# BATT_INPUT_REVISION.net
KiCad netlist of a schematic drawn in EAGLE
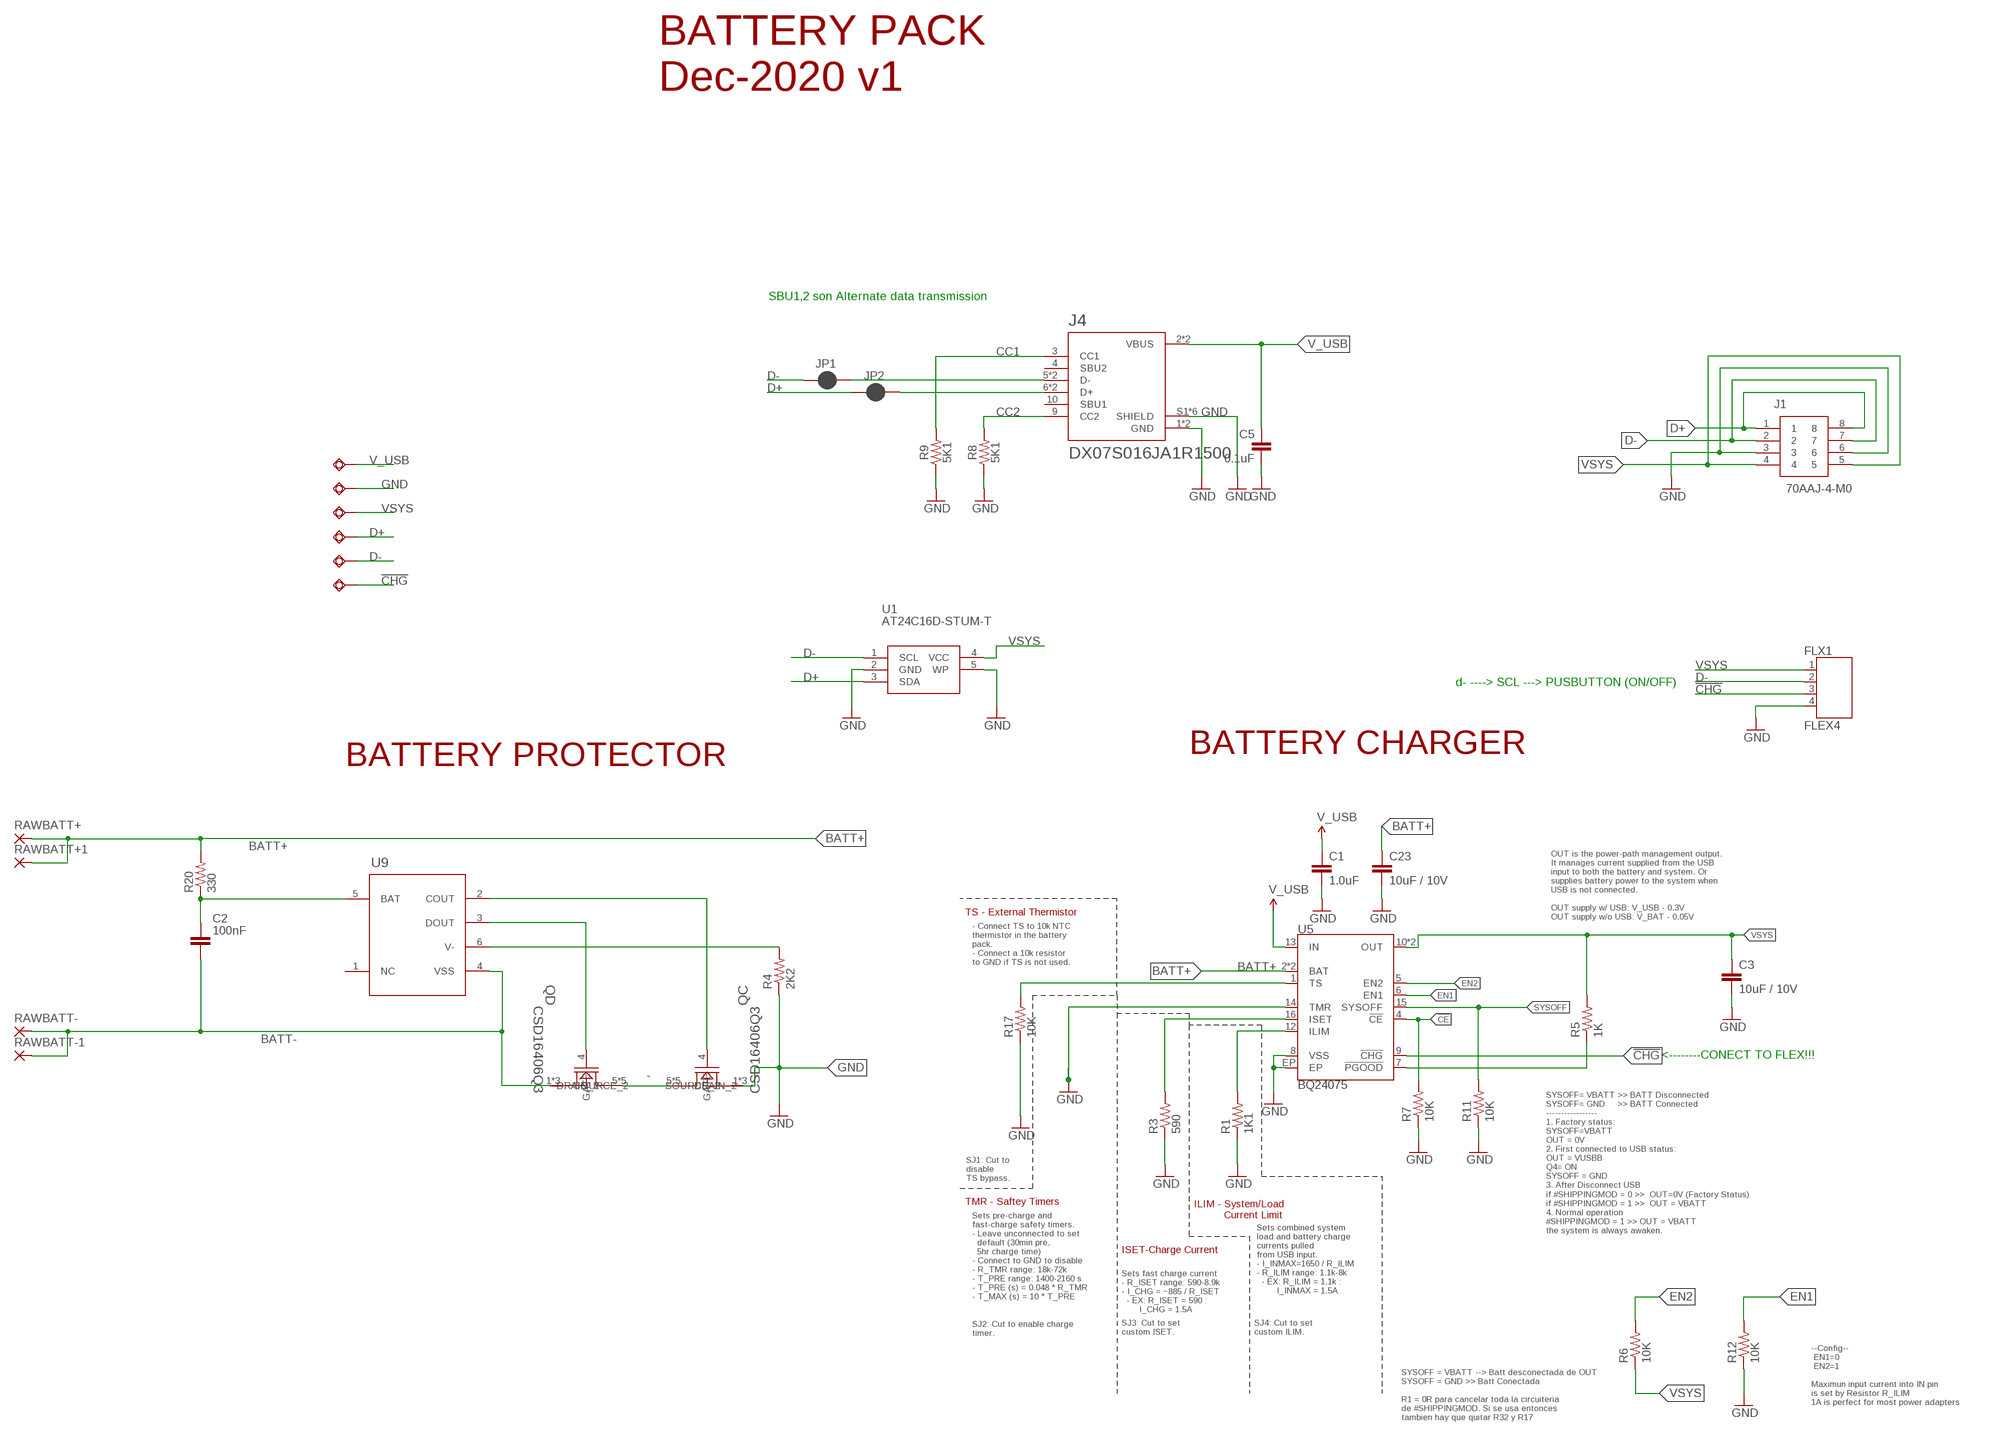
[diagram p0: schematic, sheet 1]

(export (version "E")
  (design (tool "Eeschema 10.0.6"))
  (components
    (comp (ref "!CHG!")
      (value "TESTPAD_TPSQB1,27")
      (footprint "eagle-import:TESTPAD_B1,27")
      (libsource (lib "eagle-import") (part "TESTPAD_TPSQB1,27"))
    )
    (comp (ref "C1")
      (value "1.0uF")
      (footprint "eagle-import:0603")
      (libsource (lib "eagle-import") (part "1.0UF-0603-16V-10%"))
    )
    (comp (ref "C2")
      (value "100nF")
      (footprint "eagle-import:CAPC1608X85")
      (libsource (lib "eagle-import") (part "CCHIP-0603(1608-METRIC)_"))
    )
    (comp (ref "C3")
      (value "10uF / 10V")
      (footprint "eagle-import:0805-CAP")
      (libsource (lib "eagle-import") (part "10UF10V10%(0805)"))
    )
    (comp (ref "C5")
      (value "0.1uF")
      (footprint "eagle-import:0603")
      (libsource (lib "eagle-import") (part "0.1UF-0603-25V-(+80/-20%)"))
    )
    (comp (ref "C23")
      (value "10uF / 10V")
      (footprint "eagle-import:0805-CAP")
      (libsource (lib "eagle-import") (part "10UF10V10%(0805)"))
    )
    (comp (ref "D+")
      (value "TESTPAD_TPSQB1,27")
      (footprint "eagle-import:TESTPAD_B1,27")
      (libsource (lib "eagle-import") (part "TESTPAD_TPSQB1,27"))
    )
    (comp (ref "D-")
      (value "TESTPAD_TPSQB1,27")
      (footprint "eagle-import:TESTPAD_B1,27")
      (libsource (lib "eagle-import") (part "TESTPAD_TPSQB1,27"))
    )
    (comp (ref "FLX1")
      (value "FLEX4")
      (footprint "eagle-import:FLEX4")
      (libsource (lib "eagle-import") (part "FLEX4"))
    )
    (comp (ref "GND")
      (value "TESTPAD_TPSQB1,27")
      (footprint "eagle-import:TESTPAD_B1,27")
      (libsource (lib "eagle-import") (part "TESTPAD_TPSQB1,27"))
    )
    (comp (ref "J1")
      (value "70AAJ-4-M0")
      (footprint "eagle-import:70AAJ4M0")
      (fields (field (name "MOUSER_PART_NUMBER") "652-70AAJ-4-M0"))
      (libsource (lib "eagle-import") (part "70AAJ-4-M0"))
    )
    (comp (ref "J4")
      (value "DX07S016JA1R1500")
      (footprint "eagle-import:JAE_DX07S016JA1R1500")
      (fields
        (field (name "DIGI-KEY_PART_NUMBER") "670-DX07S016JA1R1500CT-ND")
        (field (name "MF") "JAE Electronics")
      )
      (libsource (lib "eagle-import") (part "DX07S016JA1R1500"))
    )
    (comp (ref "JP1")
      (value "JUMPER-SMT_2_NC_PASTE_SILK")
      (footprint "eagle-import:SMT-JUMPER_2_NC_PASTE_SILK")
      (libsource (lib "eagle-import") (part "JUMPER-SMT_2_NC_PASTE_SILK"))
    )
    (comp (ref "JP2")
      (value "JUMPER-SMT_2_NC_PASTE_SILK")
      (footprint "eagle-import:SMT-JUMPER_2_NC_PASTE_SILK")
      (libsource (lib "eagle-import") (part "JUMPER-SMT_2_NC_PASTE_SILK"))
    )
    (comp (ref "QC")
      (value "CSD16406Q3")
      (footprint "eagle-import:DQG0008A")
      (libsource (lib "eagle-import") (part "CSD16406Q3"))
    )
    (comp (ref "QD")
      (value "CSD16406Q3")
      (footprint "eagle-import:DQG0008A")
      (libsource (lib "eagle-import") (part "CSD16406Q3"))
    )
    (comp (ref "R1")
      (value "1K1")
      (footprint "eagle-import:0402")
      (libsource (lib "eagle-import") (part "RESISTOR0402"))
    )
    (comp (ref "R3")
      (value "590")
      (footprint "eagle-import:0402")
      (libsource (lib "eagle-import") (part "RESISTOR0402"))
    )
    (comp (ref "R4")
      (value "2K2")
      (footprint "eagle-import:0402")
      (libsource (lib "eagle-import") (part "RESISTOR0402"))
    )
    (comp (ref "R5")
      (value "1K")
      (footprint "eagle-import:0402")
      (libsource (lib "eagle-import") (part "RESISTOR0402"))
    )
    (comp (ref "R6")
      (value "10K")
      (footprint "eagle-import:0402")
      (libsource (lib "eagle-import") (part "RESISTOR0402"))
    )
    (comp (ref "R7")
      (value "10K")
      (footprint "eagle-import:0402")
      (libsource (lib "eagle-import") (part "RESISTOR0402"))
    )
    (comp (ref "R8")
      (value "5K1")
      (footprint "eagle-import:0402")
      (libsource (lib "eagle-import") (part "RESISTOR0402"))
    )
    (comp (ref "R9")
      (value "5K1")
      (footprint "eagle-import:0402")
      (libsource (lib "eagle-import") (part "RESISTOR0402"))
    )
    (comp (ref "R11")
      (value "10K")
      (footprint "eagle-import:0402")
      (libsource (lib "eagle-import") (part "RESISTOR0402"))
    )
    (comp (ref "R12")
      (value "10K")
      (footprint "eagle-import:0402")
      (libsource (lib "eagle-import") (part "RESISTOR0402"))
    )
    (comp (ref "R17")
      (value "10K")
      (footprint "eagle-import:0402")
      (libsource (lib "eagle-import") (part "RESISTOR0402"))
    )
    (comp (ref "R20")
      (value "330")
      (footprint "eagle-import:0402")
      (libsource (lib "eagle-import") (part "RESISTOR0402"))
    )
    (comp (ref "RAWBATT+")
      (value "SMD5")
      (footprint "eagle-import:SMD2,54-5,08")
      (libsource (lib "eagle-import") (part "SMD5"))
    )
    (comp (ref "RAWBATT+1")
      (value "SMD5")
      (footprint "eagle-import:SMD2,54-5,08")
      (libsource (lib "eagle-import") (part "SMD5"))
    )
    (comp (ref "RAWBATT-")
      (value "SMD5")
      (footprint "eagle-import:SMD2,54-5,08")
      (libsource (lib "eagle-import") (part "SMD5"))
    )
    (comp (ref "RAWBATT-1")
      (value "SMD5")
      (footprint "eagle-import:SMD2,54-5,08")
      (libsource (lib "eagle-import") (part "SMD5"))
    )
    (comp (ref "U1")
      (value "AT24C16D-STUM-T")
      (footprint "eagle-import:SOT95P280X100-5N")
      (fields (field (name "MOUSER_PART_NUMBER") "556-AT24C16D-STUM-T"))
      (libsource (lib "eagle-import") (part "AT24C16D-STUM-T"))
    )
    (comp (ref "U5")
      (value "BQ24075")
      (footprint "eagle-import:PVQFN-N16")
      (libsource (lib "eagle-import") (part "BQ24075"))
    )
    (comp (ref "U9")
      (value "Value")
      (footprint "eagle-import:DSE0006A")
      (fields (field (name "MANUFACTURER") "Texas Instruments") (field (name "PARTNUMBER") "BQ29705DSER"))
      (libsource (lib "eagle-import") (part "BQ29700DSER"))
    )
    (comp (ref "VSYS")
      (value "TESTPAD_TPSQB1,27")
      (footprint "eagle-import:TESTPAD_B1,27")
      (libsource (lib "eagle-import") (part "TESTPAD_TPSQB1,27"))
    )
    (comp (ref "V_USB")
      (value "TESTPAD_TPSQB1,27")
      (footprint "eagle-import:TESTPAD_B1,27")
      (libsource (lib "eagle-import") (part "TESTPAD_TPSQB1,27"))
    )
  )
  (nets
    (net (code "1") (name "/-") (class "Default")
      (node (ref "QC") (pin "5") (pinfunction "DRAIN_2_5") (pintype "passive"))
      (node (ref "QC") (pin "6") (pinfunction "DRAIN_2_6") (pintype "passive"))
      (node (ref "QC") (pin "7") (pinfunction "DRAIN_2_7") (pintype "passive"))
      (node (ref "QC") (pin "8") (pinfunction "DRAIN_2_8") (pintype "passive"))
      (node (ref "QC") (pin "9") (pinfunction "DRAIN_2_9") (pintype "passive"))
      (node (ref "QD") (pin "5") (pinfunction "DRAIN_2_5") (pintype "passive"))
      (node (ref "QD") (pin "6") (pinfunction "DRAIN_2_6") (pintype "passive"))
      (node (ref "QD") (pin "7") (pinfunction "DRAIN_2_7") (pintype "passive"))
      (node (ref "QD") (pin "8") (pinfunction "DRAIN_2_8") (pintype "passive"))
      (node (ref "QD") (pin "9") (pinfunction "DRAIN_2_9") (pintype "passive"))
    )
    (net (code "2") (name "/BATT-") (class "Default")
      (node (ref "C2") (pin "2") (pinfunction "2_2") (pintype "passive"))
      (node (ref "QD") (pin "1") (pinfunction "SOURCE_2_1") (pintype "passive"))
      (node (ref "QD") (pin "2") (pinfunction "SOURCE_2_2") (pintype "passive"))
      (node (ref "QD") (pin "3") (pinfunction "SOURCE_2_3") (pintype "passive"))
      (node (ref "RAWBATT-") (pin "1") (pinfunction "P_1") (pintype "passive"))
      (node (ref "RAWBATT-1") (pin "1") (pinfunction "P_1") (pintype "passive"))
      (node (ref "U9") (pin "4") (pinfunction "VSS_4") (pintype "power_in"))
    )
    (net (code "3") (name "/CC1") (class "Default")
      (node (ref "J4") (pin "3") (pinfunction "CC1_3") (pintype "passive"))
      (node (ref "R9") (pin "2") (pinfunction "2_2") (pintype "passive"))
    )
    (net (code "4") (name "/CC2") (class "Default")
      (node (ref "J4") (pin "9") (pinfunction "CC2_9") (pintype "passive"))
      (node (ref "R8") (pin "2") (pinfunction "2_2") (pintype "passive"))
    )
    (net (code "5") (name "/~{CE}") (class "Default")
      (node (ref "R7") (pin "2") (pinfunction "2_2") (pintype "passive"))
      (node (ref "U5") (pin "4") (pinfunction "~{CE}_4") (pintype "bidirectional"))
    )
    (net (code "6") (name "/~{CHG}") (class "Default")
      (node (ref "!CHG!") (pin "TP") (pinfunction "TP_TP") (pintype "input"))
      (node (ref "FLX1") (pin "3") (pinfunction "3_3") (pintype "passive"))
      (node (ref "U5") (pin "9") (pinfunction "~{CHG}_9") (pintype "bidirectional"))
    )
    (net (code "7") (name "BATT+") (class "Default")
      (node (ref "C23") (pin "1") (pinfunction "1_1") (pintype "passive"))
      (node (ref "R20") (pin "2") (pinfunction "2_2") (pintype "passive"))
      (node (ref "RAWBATT+") (pin "1") (pinfunction "P_1") (pintype "passive"))
      (node (ref "RAWBATT+1") (pin "1") (pinfunction "P_1") (pintype "passive"))
      (node (ref "U5") (pin "2") (pinfunction "BAT_2") (pintype "bidirectional"))
      (node (ref "U5") (pin "3") (pinfunction "BAT_3") (pintype "bidirectional"))
    )
    (net (code "8") (name "D+") (class "Default")
      (node (ref "D+") (pin "TP") (pinfunction "TP_TP") (pintype "input"))
      (node (ref "J1") (pin "1") (pinfunction "1_1") (pintype "bidirectional"))
      (node (ref "J1") (pin "8") (pinfunction "8_8") (pintype "bidirectional"))
      (node (ref "JP2") (pin "1") (pinfunction "1_1") (pintype "passive"))
      (node (ref "U1") (pin "3") (pinfunction "SDA_3") (pintype "bidirectional"))
    )
    (net (code "9") (name "D-") (class "Default")
      (node (ref "D-") (pin "TP") (pinfunction "TP_TP") (pintype "input"))
      (node (ref "FLX1") (pin "2") (pinfunction "2_2") (pintype "passive"))
      (node (ref "J1") (pin "2") (pinfunction "2_2") (pintype "bidirectional"))
      (node (ref "J1") (pin "7") (pinfunction "7_7") (pintype "bidirectional"))
      (node (ref "JP1") (pin "1") (pinfunction "1_1") (pintype "passive"))
      (node (ref "U1") (pin "1") (pinfunction "SCL_1") (pintype "bidirectional"))
    )
    (net (code "10") (name "EN1") (class "Default")
      (node (ref "R12") (pin "2") (pinfunction "2_2") (pintype "passive"))
      (node (ref "U5") (pin "6") (pinfunction "EN1_6") (pintype "bidirectional"))
    )
    (net (code "11") (name "EN2") (class "Default")
      (node (ref "R6") (pin "2") (pinfunction "2_2") (pintype "passive"))
      (node (ref "U5") (pin "5") (pinfunction "EN2_5") (pintype "bidirectional"))
    )
    (net (code "12") (name "GND") (class "Default")
      (node (ref "C1") (pin "2") (pinfunction "2_2") (pintype "passive"))
      (node (ref "C23") (pin "2") (pinfunction "2_2") (pintype "passive"))
      (node (ref "C3") (pin "2") (pinfunction "2_2") (pintype "passive"))
      (node (ref "C5") (pin "2") (pinfunction "2_2") (pintype "passive"))
      (node (ref "FLX1") (pin "4") (pinfunction "4_4") (pintype "passive"))
      (node (ref "GND") (pin "TP") (pinfunction "TP_TP") (pintype "input"))
      (node (ref "J1") (pin "3") (pinfunction "3_3") (pintype "bidirectional"))
      (node (ref "J1") (pin "6") (pinfunction "6_6") (pintype "bidirectional"))
      (node (ref "J4") (pin "1") (pinfunction "GND_1") (pintype "power_in"))
      (node (ref "J4") (pin "12") (pinfunction "GND_12") (pintype "power_in"))
      (node (ref "J4") (pin "S1") (pinfunction "SHIELD_S1") (pintype "passive"))
      (node (ref "J4") (pin "S2") (pinfunction "SHIELD_S2") (pintype "passive"))
      (node (ref "J4") (pin "S3") (pinfunction "SHIELD_S3") (pintype "passive"))
      (node (ref "J4") (pin "S4") (pinfunction "SHIELD_S4") (pintype "passive"))
      (node (ref "J4") (pin "S5") (pinfunction "SHIELD_S5") (pintype "passive"))
      (node (ref "J4") (pin "S6") (pinfunction "SHIELD_S6") (pintype "passive"))
      (node (ref "QC") (pin "1") (pinfunction "SOURCE_2_1") (pintype "passive"))
      (node (ref "QC") (pin "2") (pinfunction "SOURCE_2_2") (pintype "passive"))
      (node (ref "QC") (pin "3") (pinfunction "SOURCE_2_3") (pintype "passive"))
      (node (ref "R1") (pin "1") (pinfunction "1_1") (pintype "passive"))
      (node (ref "R11") (pin "1") (pinfunction "1_1") (pintype "passive"))
      (node (ref "R12") (pin "1") (pinfunction "1_1") (pintype "passive"))
      (node (ref "R17") (pin "1") (pinfunction "1_1") (pintype "passive"))
      (node (ref "R3") (pin "1") (pinfunction "1_1") (pintype "passive"))
      (node (ref "R4") (pin "1") (pinfunction "1_1") (pintype "passive"))
      (node (ref "R7") (pin "1") (pinfunction "1_1") (pintype "passive"))
      (node (ref "R8") (pin "1") (pinfunction "1_1") (pintype "passive"))
      (node (ref "R9") (pin "1") (pinfunction "1_1") (pintype "passive"))
      (node (ref "U1") (pin "2") (pinfunction "GND_2") (pintype "power_in"))
      (node (ref "U1") (pin "5") (pinfunction "WP_5") (pintype "input"))
      (node (ref "U5") (pin "14") (pinfunction "TMR_14") (pintype "bidirectional"))
      (node (ref "U5") (pin "8") (pinfunction "VSS_8") (pintype "bidirectional"))
      (node (ref "U5") (pin "EP") (pinfunction "EP_EP") (pintype "bidirectional"))
    )
    (net (code "13") (name "Net-(J4-D+-Pad6)") (class "Default")
      (node (ref "J4") (pin "6") (pinfunction "D+_6") (pintype "passive"))
      (node (ref "J4") (pin "7") (pinfunction "D+_7") (pintype "passive"))
      (node (ref "JP2") (pin "2") (pinfunction "2_2") (pintype "passive"))
    )
    (net (code "14") (name "Net-(J4-D--Pad5)") (class "Default")
      (node (ref "J4") (pin "5") (pinfunction "D-_5") (pintype "passive"))
      (node (ref "J4") (pin "8") (pinfunction "D-_8") (pintype "passive"))
      (node (ref "JP1") (pin "2") (pinfunction "2_2") (pintype "passive"))
    )
    (net (code "15") (name "Net-(QC-GATE)") (class "Default")
      (node (ref "QC") (pin "4") (pinfunction "GATE_4") (pintype "passive"))
      (node (ref "U9") (pin "2") (pinfunction "COUT_2") (pintype "output"))
    )
    (net (code "16") (name "Net-(QD-GATE)") (class "Default")
      (node (ref "QD") (pin "4") (pinfunction "GATE_4") (pintype "passive"))
      (node (ref "U9") (pin "3") (pinfunction "DOUT_3") (pintype "output"))
    )
    (net (code "17") (name "Net-(U5-ILIM)") (class "Default")
      (node (ref "R1") (pin "2") (pinfunction "2_2") (pintype "passive"))
      (node (ref "U5") (pin "12") (pinfunction "ILIM_12") (pintype "bidirectional"))
    )
    (net (code "18") (name "Net-(U5-ISET)") (class "Default")
      (node (ref "R3") (pin "2") (pinfunction "2_2") (pintype "passive"))
      (node (ref "U5") (pin "16") (pinfunction "ISET_16") (pintype "bidirectional"))
    )
    (net (code "19") (name "Net-(U5-TS)") (class "Default")
      (node (ref "R17") (pin "2") (pinfunction "2_2") (pintype "passive"))
      (node (ref "U5") (pin "1") (pinfunction "TS_1") (pintype "bidirectional"))
    )
    (net (code "20") (name "Net-(U5-~{PGOOD})") (class "Default")
      (node (ref "R5") (pin "1") (pinfunction "1_1") (pintype "passive"))
      (node (ref "U5") (pin "7") (pinfunction "~{PGOOD}_7") (pintype "bidirectional"))
    )
    (net (code "21") (name "Net-(U9-BAT)") (class "Default")
      (node (ref "C2") (pin "1") (pinfunction "1_1") (pintype "passive"))
      (node (ref "R20") (pin "1") (pinfunction "1_1") (pintype "passive"))
      (node (ref "U9") (pin "5") (pinfunction "BAT_5") (pintype "power_in"))
    )
    (net (code "22") (name "Net-(U9-V-)") (class "Default")
      (node (ref "R4") (pin "2") (pinfunction "2_2") (pintype "passive"))
      (node (ref "U9") (pin "6") (pinfunction "V-_6") (pintype "bidirectional"))
    )
    (net (code "23") (name "SYSOFF") (class "Default")
      (node (ref "R11") (pin "2") (pinfunction "2_2") (pintype "passive"))
      (node (ref "U5") (pin "15") (pinfunction "SYSOFF_15") (pintype "bidirectional"))
    )
    (net (code "24") (name "VSYS") (class "Default")
      (node (ref "C3") (pin "1") (pinfunction "1_1") (pintype "passive"))
      (node (ref "FLX1") (pin "1") (pinfunction "1_1") (pintype "passive"))
      (node (ref "J1") (pin "4") (pinfunction "4_4") (pintype "bidirectional"))
      (node (ref "J1") (pin "5") (pinfunction "5_5") (pintype "bidirectional"))
      (node (ref "R5") (pin "2") (pinfunction "2_2") (pintype "passive"))
      (node (ref "R6") (pin "1") (pinfunction "1_1") (pintype "passive"))
      (node (ref "U1") (pin "4") (pinfunction "VCC_4") (pintype "power_in"))
      (node (ref "U5") (pin "10") (pinfunction "OUT_10") (pintype "bidirectional"))
      (node (ref "U5") (pin "11") (pinfunction "OUT_11") (pintype "bidirectional"))
      (node (ref "VSYS") (pin "TP") (pinfunction "TP_TP") (pintype "input"))
    )
    (net (code "25") (name "V_USB") (class "Default")
      (node (ref "C1") (pin "1") (pinfunction "1_1") (pintype "passive"))
      (node (ref "C5") (pin "1") (pinfunction "1_1") (pintype "passive"))
      (node (ref "J4") (pin "11") (pinfunction "VBUS_11") (pintype "power_in"))
      (node (ref "J4") (pin "2") (pinfunction "VBUS_2") (pintype "power_in"))
      (node (ref "U5") (pin "13") (pinfunction "IN_13") (pintype "bidirectional"))
      (node (ref "V_USB") (pin "TP") (pinfunction "TP_TP") (pintype "input"))
    )
    (net (code "26") (name "unconnected-(J4-SBU1-Pad10)") (class "Default")
      (node (ref "J4") (pin "10") (pinfunction "SBU1_10") (pintype "passive"))
    )
    (net (code "27") (name "unconnected-(J4-SBU2-Pad4)") (class "Default")
      (node (ref "J4") (pin "4") (pinfunction "SBU2_4") (pintype "passive"))
    )
    (net (code "28") (name "unconnected-(U9-NC-Pad1)") (class "Default")
      (node (ref "U9") (pin "1") (pinfunction "NC_1") (pintype "passive"))
    )
  )
)
